# tick-mk-4_6_1.net
KiCad netlist of a schematic drawn in EAGLE
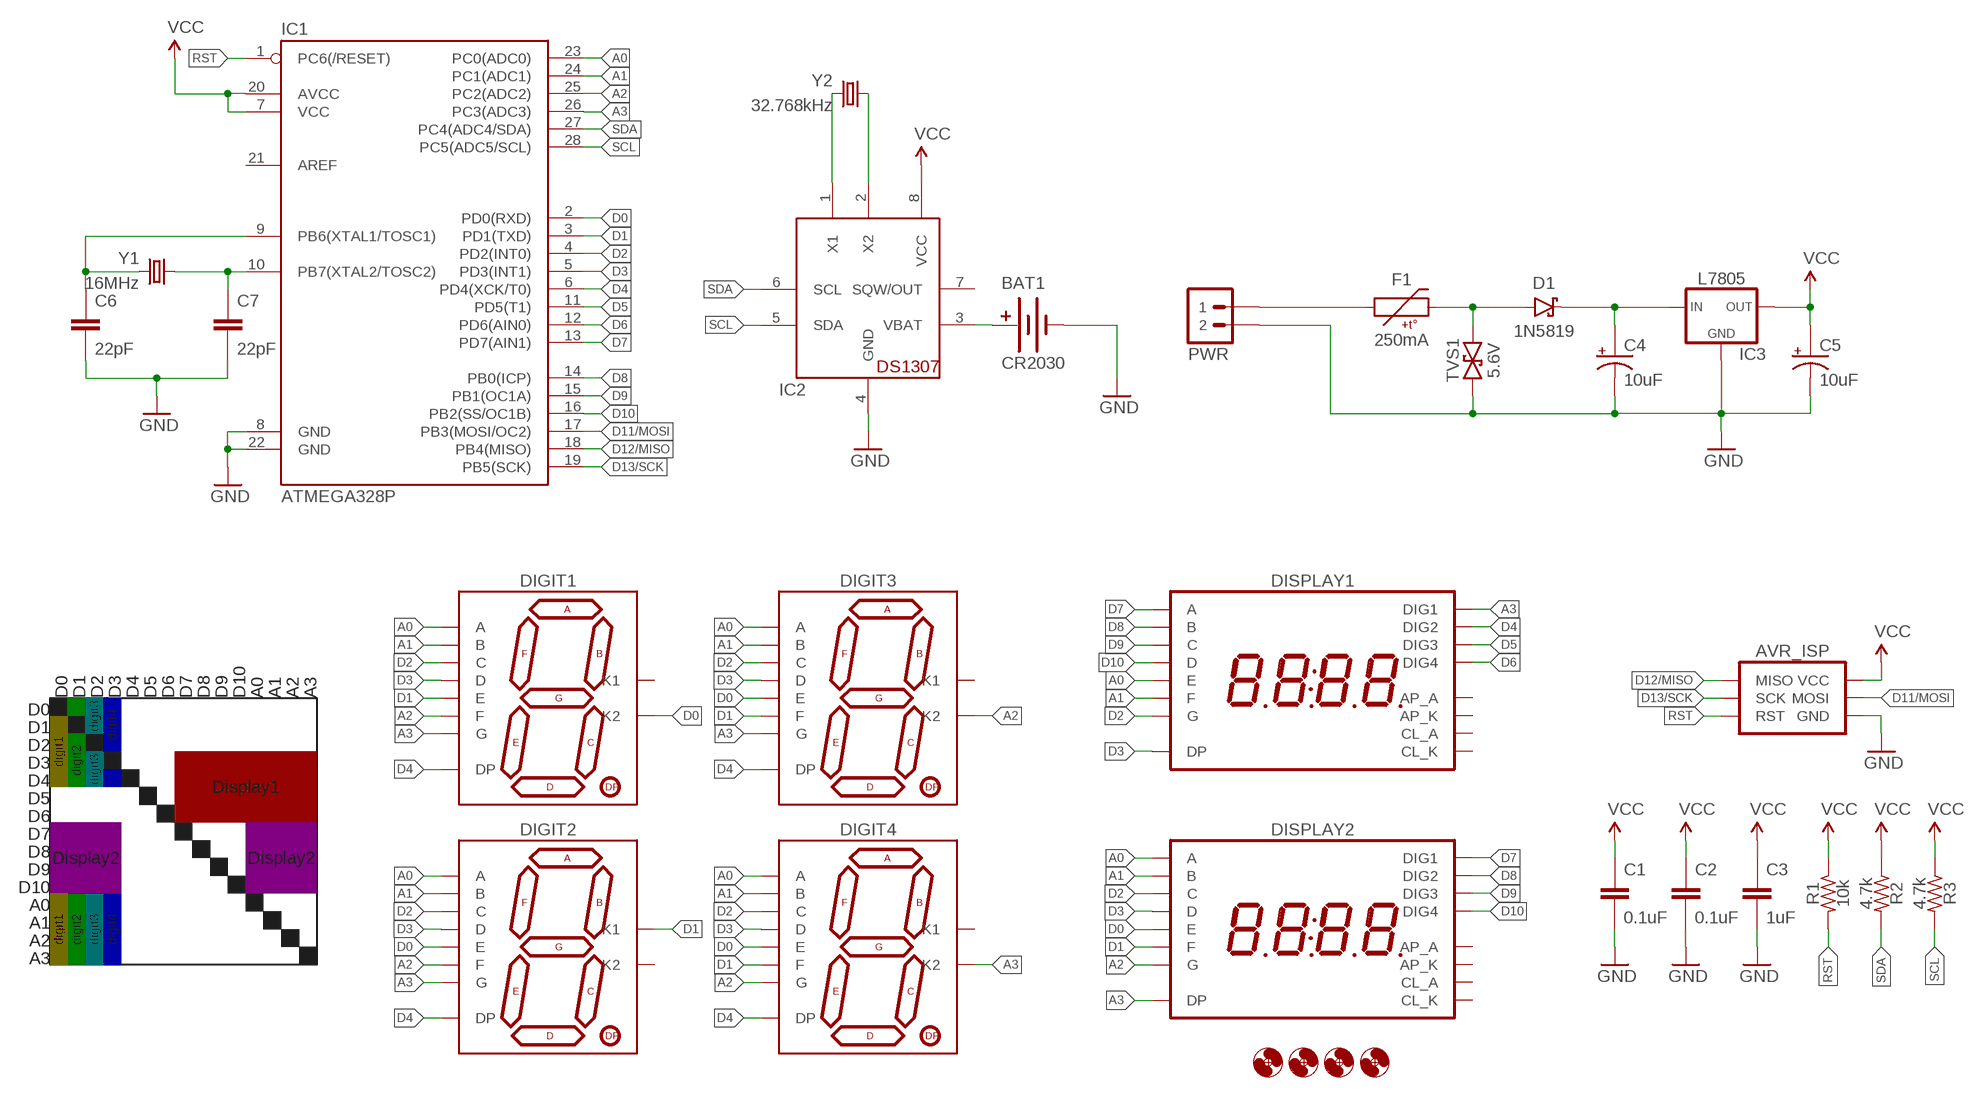
[diagram p0: schematic, sheet 1]

(export (version "E")
  (design (tool "Eeschema 10.0.6"))
  (components
    (comp (ref "AVR_ISP")
      (value "AVR_SPI_PRG_6PTH")
      (footprint "eagle-import:2X3")
      (libsource (lib "eagle-import") (part "AVR_SPI_PRG_6PTH"))
    )
    (comp (ref "BAT1")
      (value "CR2030")
      (footprint "eagle-import:BATTCON_20MM_MINE")
      (libsource (lib "eagle-import") (part "BATTERY20MMSMD-MINE"))
    )
    (comp (ref "C1")
      (value "0.1uF")
      (footprint "eagle-import:C025-024X044")
      (libsource (lib "eagle-import") (part "CAPACITOR-CERAMIC025-024X044"))
    )
    (comp (ref "C2")
      (value "0.1uF")
      (footprint "eagle-import:C025-024X044")
      (libsource (lib "eagle-import") (part "CAPACITOR-CERAMIC025-024X044"))
    )
    (comp (ref "C3")
      (value "1uF")
      (footprint "eagle-import:C025-024X044")
      (libsource (lib "eagle-import") (part "CAPACITOR-CERAMIC025-024X044"))
    )
    (comp (ref "C4")
      (value "10uF")
      (footprint "eagle-import:E2-5")
      (libsource (lib "eagle-import") (part "CAPACITOR-POLARIZEDE2-5"))
    )
    (comp (ref "C5")
      (value "10uF")
      (footprint "eagle-import:E2-5")
      (libsource (lib "eagle-import") (part "CAPACITOR-POLARIZEDE2-5"))
    )
    (comp (ref "C6")
      (value "22pF")
      (footprint "eagle-import:C025-024X044")
      (libsource (lib "eagle-import") (part "CAPACITOR-CERAMIC025-024X044"))
    )
    (comp (ref "C7")
      (value "22pF")
      (footprint "eagle-import:C025-024X044")
      (libsource (lib "eagle-import") (part "CAPACITOR-CERAMIC025-024X044"))
    )
    (comp (ref "D1")
      (value "1N5819")
      (footprint "eagle-import:DIODE-10.16MM")
      (libsource (lib "eagle-import") (part "DIODE-SCHOTTKYPTH-10.16MM"))
    )
    (comp (ref "DIGIT1")
      (value "7SEG_1DIGPTH-25.4MM-BARE")
      (footprint "eagle-import:7SEG_1DIG_25.4MM_NOSILK")
      (libsource (lib "eagle-import") (part "7SEG_1DIGPTH-25.4MM-BARE"))
    )
    (comp (ref "DIGIT2")
      (value "7SEG_1DIGPTH-25.4MM-BARE")
      (footprint "eagle-import:7SEG_1DIG_25.4MM_NOSILK")
      (libsource (lib "eagle-import") (part "7SEG_1DIGPTH-25.4MM-BARE"))
    )
    (comp (ref "DIGIT3")
      (value "7SEG_1DIGPTH-25.4MM-BARE")
      (footprint "eagle-import:7SEG_1DIG_25.4MM_NOSILK")
      (libsource (lib "eagle-import") (part "7SEG_1DIGPTH-25.4MM-BARE"))
    )
    (comp (ref "DIGIT4")
      (value "7SEG_1DIGPTH-25.4MM-BARE")
      (footprint "eagle-import:7SEG_1DIG_25.4MM_NOSILK")
      (libsource (lib "eagle-import") (part "7SEG_1DIGPTH-25.4MM-BARE"))
    )
    (comp (ref "DISPLAY1")
      (value "7SEG_4DIGIT_COLON_APOS")
      (footprint "eagle-import:7SEG_4DIG_10MM")
      (libsource (lib "eagle-import") (part "7SEG_4DIGIT_COLON_APOS"))
    )
    (comp (ref "DISPLAY2")
      (value "7SEG_4DIGIT_COLON_APOS")
      (footprint "eagle-import:7SEG_4DIG_10MM")
      (libsource (lib "eagle-import") (part "7SEG_4DIGIT_COLON_APOS"))
    )
    (comp (ref "F1")
      (value "250mA")
      (footprint "eagle-import:PTC-PTH-5.08MM")
      (libsource (lib "eagle-import") (part "PTCPTH-5.08MM"))
    )
    (comp (ref "H1")
      (value "HOLE#2")
      (footprint "eagle-import:HOLE-#2")
      (libsource (lib "eagle-import") (part "HOLE#2"))
    )
    (comp (ref "H2")
      (value "HOLE#2")
      (footprint "eagle-import:HOLE-#2")
      (libsource (lib "eagle-import") (part "HOLE#2"))
    )
    (comp (ref "H3")
      (value "HOLE#2")
      (footprint "eagle-import:HOLE-#2")
      (libsource (lib "eagle-import") (part "HOLE#2"))
    )
    (comp (ref "H4")
      (value "HOLE#2")
      (footprint "eagle-import:HOLE-#2")
      (libsource (lib "eagle-import") (part "HOLE#2"))
    )
    (comp (ref "IC1")
      (value "ATMEGA328P")
      (footprint "eagle-import:DIL28-3")
      (libsource (lib "eagle-import") (part "ATMEGA328P_PDIP"))
    )
    (comp (ref "IC2")
      (value "DS1307")
      (footprint "eagle-import:DIL08")
      (libsource (lib "eagle-import") (part "DS1307"))
    )
    (comp (ref "IC3")
      (value "L7805")
      (footprint "eagle-import:TO220-IGO-THERMPAD")
      (libsource (lib "eagle-import") (part "V_REG_78XXTO-220-THERMPAD"))
    )
    (comp (ref "PWR")
      (value "M02JST-PTH-VERT")
      (footprint "eagle-import:JST-2-PH-VERT-PTH")
      (libsource (lib "eagle-import") (part "M02JST-PTH-VERT"))
    )
    (comp (ref "R1")
      (value "10k")
      (footprint "eagle-import:RESISTOR-AXIAL-PTH-7.62MM")
      (libsource (lib "eagle-import") (part "RESISTORPTH-AXIAL-7.62MM"))
    )
    (comp (ref "R2")
      (value "4.7k")
      (footprint "eagle-import:RESISTOR-AXIAL-PTH-6.35MM")
      (libsource (lib "eagle-import") (part "RESISTORPTH-AXIAL-6.35MM"))
    )
    (comp (ref "R3")
      (value "4.7k")
      (footprint "eagle-import:RESISTOR-AXIAL-PTH-6.35MM")
      (libsource (lib "eagle-import") (part "RESISTORPTH-AXIAL-6.35MM"))
    )
    (comp (ref "TVS1")
      (value "5.6V")
      (footprint "eagle-import:DO-41-TVS-BI-10.16MM")
      (libsource (lib "eagle-import") (part "TVSDO-41-10.16MM"))
    )
    (comp (ref "Y1")
      (value "16MHz")
      (footprint "eagle-import:HC49U-V")
      (libsource (lib "eagle-import") (part "CRYSTALHC49UV"))
    )
    (comp (ref "Y2")
      (value "32.768kHz")
      (footprint "eagle-import:TC26H")
      (libsource (lib "eagle-import") (part "CRYSTALTC26H"))
    )
  )
  (nets
    (net (code "1") (name "A0") (class "Default")
      (node (ref "DIGIT1") (pin "7") (pinfunction "A_7") (pintype "bidirectional"))
      (node (ref "DIGIT2") (pin "7") (pinfunction "A_7") (pintype "bidirectional"))
      (node (ref "DIGIT3") (pin "7") (pinfunction "A_7") (pintype "bidirectional"))
      (node (ref "DIGIT4") (pin "7") (pinfunction "A_7") (pintype "bidirectional"))
      (node (ref "DISPLAY1") (pin "5") (pinfunction "E_5") (pintype "passive"))
      (node (ref "DISPLAY2") (pin "14") (pinfunction "A_14") (pintype "passive"))
      (node (ref "IC1") (pin "23") (pinfunction "PC0(ADC0)_23") (pintype "bidirectional"))
    )
    (net (code "2") (name "A1") (class "Default")
      (node (ref "DIGIT1") (pin "6") (pinfunction "B_6") (pintype "bidirectional"))
      (node (ref "DIGIT2") (pin "6") (pinfunction "B_6") (pintype "bidirectional"))
      (node (ref "DIGIT3") (pin "6") (pinfunction "B_6") (pintype "bidirectional"))
      (node (ref "DIGIT4") (pin "6") (pinfunction "B_6") (pintype "bidirectional"))
      (node (ref "DISPLAY1") (pin "11") (pinfunction "F_11") (pintype "passive"))
      (node (ref "DISPLAY2") (pin "16") (pinfunction "B_16") (pintype "passive"))
      (node (ref "IC1") (pin "24") (pinfunction "PC1(ADC1)_24") (pintype "bidirectional"))
    )
    (net (code "3") (name "A2") (class "Default")
      (node (ref "DIGIT1") (pin "9") (pinfunction "F_9") (pintype "bidirectional"))
      (node (ref "DIGIT2") (pin "9") (pinfunction "F_9") (pintype "bidirectional"))
      (node (ref "DIGIT3") (pin "8") (pinfunction "K2_8") (pintype "bidirectional"))
      (node (ref "DIGIT4") (pin "10") (pinfunction "G_10") (pintype "bidirectional"))
      (node (ref "DISPLAY2") (pin "15") (pinfunction "G_15") (pintype "passive"))
      (node (ref "IC1") (pin "25") (pinfunction "PC2(ADC2)_25") (pintype "bidirectional"))
    )
    (net (code "4") (name "A3") (class "Default")
      (node (ref "DIGIT1") (pin "10") (pinfunction "G_10") (pintype "bidirectional"))
      (node (ref "DIGIT2") (pin "10") (pinfunction "G_10") (pintype "bidirectional"))
      (node (ref "DIGIT3") (pin "10") (pinfunction "G_10") (pintype "bidirectional"))
      (node (ref "DIGIT4") (pin "8") (pinfunction "K2_8") (pintype "bidirectional"))
      (node (ref "DISPLAY1") (pin "1") (pinfunction "DIG1_1") (pintype "passive"))
      (node (ref "DISPLAY2") (pin "7") (pinfunction "DP_7") (pintype "passive"))
      (node (ref "IC1") (pin "26") (pinfunction "PC3(ADC3)_26") (pintype "bidirectional"))
    )
    (net (code "5") (name "D0") (class "Default")
      (node (ref "DIGIT1") (pin "8") (pinfunction "K2_8") (pintype "bidirectional"))
      (node (ref "DIGIT2") (pin "1") (pinfunction "E_1") (pintype "bidirectional"))
      (node (ref "DIGIT3") (pin "1") (pinfunction "E_1") (pintype "bidirectional"))
      (node (ref "DIGIT4") (pin "1") (pinfunction "E_1") (pintype "bidirectional"))
      (node (ref "DISPLAY2") (pin "5") (pinfunction "E_5") (pintype "passive"))
      (node (ref "IC1") (pin "2") (pinfunction "PD0(RXD)_2") (pintype "bidirectional"))
    )
    (net (code "6") (name "D1") (class "Default")
      (node (ref "DIGIT1") (pin "1") (pinfunction "E_1") (pintype "bidirectional"))
      (node (ref "DIGIT2") (pin "3") (pinfunction "K1_3") (pintype "bidirectional"))
      (node (ref "DIGIT3") (pin "9") (pinfunction "F_9") (pintype "bidirectional"))
      (node (ref "DIGIT4") (pin "9") (pinfunction "F_9") (pintype "bidirectional"))
      (node (ref "DISPLAY2") (pin "11") (pinfunction "F_11") (pintype "passive"))
      (node (ref "IC1") (pin "3") (pinfunction "PD1(TXD)_3") (pintype "bidirectional"))
    )
    (net (code "7") (name "D2") (class "Default")
      (node (ref "DIGIT1") (pin "4") (pinfunction "C_4") (pintype "bidirectional"))
      (node (ref "DIGIT2") (pin "4") (pinfunction "C_4") (pintype "bidirectional"))
      (node (ref "DIGIT3") (pin "4") (pinfunction "C_4") (pintype "bidirectional"))
      (node (ref "DIGIT4") (pin "4") (pinfunction "C_4") (pintype "bidirectional"))
      (node (ref "DISPLAY1") (pin "15") (pinfunction "G_15") (pintype "passive"))
      (node (ref "DISPLAY2") (pin "13") (pinfunction "C_13") (pintype "passive"))
      (node (ref "IC1") (pin "4") (pinfunction "PD2(INT0)_4") (pintype "bidirectional"))
    )
    (net (code "8") (name "D3") (class "Default")
      (node (ref "DIGIT1") (pin "2") (pinfunction "D_2") (pintype "bidirectional"))
      (node (ref "DIGIT2") (pin "2") (pinfunction "D_2") (pintype "bidirectional"))
      (node (ref "DIGIT3") (pin "2") (pinfunction "D_2") (pintype "bidirectional"))
      (node (ref "DIGIT4") (pin "2") (pinfunction "D_2") (pintype "bidirectional"))
      (node (ref "DISPLAY1") (pin "7") (pinfunction "DP_7") (pintype "passive"))
      (node (ref "DISPLAY2") (pin "3") (pinfunction "D_3") (pintype "passive"))
      (node (ref "IC1") (pin "5") (pinfunction "PD3(INT1)_5") (pintype "bidirectional"))
    )
    (net (code "9") (name "D4") (class "Default")
      (node (ref "DIGIT1") (pin "5") (pinfunction "DP_5") (pintype "bidirectional"))
      (node (ref "DIGIT2") (pin "5") (pinfunction "DP_5") (pintype "bidirectional"))
      (node (ref "DIGIT3") (pin "5") (pinfunction "DP_5") (pintype "bidirectional"))
      (node (ref "DIGIT4") (pin "5") (pinfunction "DP_5") (pintype "bidirectional"))
      (node (ref "DISPLAY1") (pin "2") (pinfunction "DIG2_2") (pintype "passive"))
      (node (ref "IC1") (pin "6") (pinfunction "PD4(XCK/T0)_6") (pintype "bidirectional"))
    )
    (net (code "10") (name "D5") (class "Default")
      (node (ref "DISPLAY1") (pin "6") (pinfunction "DIG3_6") (pintype "passive"))
      (node (ref "IC1") (pin "11") (pinfunction "PD5(T1)_11") (pintype "bidirectional"))
    )
    (net (code "11") (name "D6") (class "Default")
      (node (ref "DISPLAY1") (pin "8") (pinfunction "DIG4_8") (pintype "passive"))
      (node (ref "IC1") (pin "12") (pinfunction "PD6(AIN0)_12") (pintype "bidirectional"))
    )
    (net (code "12") (name "D7") (class "Default")
      (node (ref "DISPLAY1") (pin "14") (pinfunction "A_14") (pintype "passive"))
      (node (ref "DISPLAY2") (pin "1") (pinfunction "DIG1_1") (pintype "passive"))
      (node (ref "IC1") (pin "13") (pinfunction "PD7(AIN1)_13") (pintype "bidirectional"))
    )
    (net (code "13") (name "D8") (class "Default")
      (node (ref "DISPLAY1") (pin "16") (pinfunction "B_16") (pintype "passive"))
      (node (ref "DISPLAY2") (pin "2") (pinfunction "DIG2_2") (pintype "passive"))
      (node (ref "IC1") (pin "14") (pinfunction "PB0(ICP)_14") (pintype "bidirectional"))
    )
    (net (code "14") (name "D9") (class "Default")
      (node (ref "DISPLAY1") (pin "13") (pinfunction "C_13") (pintype "passive"))
      (node (ref "DISPLAY2") (pin "6") (pinfunction "DIG3_6") (pintype "passive"))
      (node (ref "IC1") (pin "15") (pinfunction "PB1(OC1A)_15") (pintype "bidirectional"))
    )
    (net (code "15") (name "D10") (class "Default")
      (node (ref "DISPLAY1") (pin "3") (pinfunction "D_3") (pintype "passive"))
      (node (ref "DISPLAY2") (pin "8") (pinfunction "DIG4_8") (pintype "passive"))
      (node (ref "IC1") (pin "16") (pinfunction "PB2(SS/OC1B)_16") (pintype "bidirectional"))
    )
    (net (code "16") (name "D11{slash}MOSI") (class "Default")
      (node (ref "AVR_ISP") (pin "4") (pinfunction "MOSI_4") (pintype "passive"))
      (node (ref "IC1") (pin "17") (pinfunction "PB3(MOSI/OC2)_17") (pintype "bidirectional"))
    )
    (net (code "17") (name "D12{slash}MISO") (class "Default")
      (node (ref "AVR_ISP") (pin "1") (pinfunction "MISO_1") (pintype "passive"))
      (node (ref "IC1") (pin "18") (pinfunction "PB4(MISO)_18") (pintype "bidirectional"))
    )
    (net (code "18") (name "D13{slash}SCK") (class "Default")
      (node (ref "AVR_ISP") (pin "3") (pinfunction "SCK_3") (pintype "passive"))
      (node (ref "IC1") (pin "19") (pinfunction "PB5(SCK)_19") (pintype "bidirectional"))
    )
    (net (code "19") (name "GND") (class "Default")
      (node (ref "AVR_ISP") (pin "6") (pinfunction "GND_6") (pintype "passive"))
      (node (ref "BAT1") (pin "BOTTOM") (pinfunction "-_BOTTOM") (pintype "power_in"))
      (node (ref "C1") (pin "2") (pinfunction "2_2") (pintype "passive"))
      (node (ref "C2") (pin "2") (pinfunction "2_2") (pintype "passive"))
      (node (ref "C3") (pin "2") (pinfunction "2_2") (pintype "passive"))
      (node (ref "C4") (pin "-") (pinfunction "-_-") (pintype "passive"))
      (node (ref "C5") (pin "-") (pinfunction "-_-") (pintype "passive"))
      (node (ref "C6") (pin "2") (pinfunction "2_2") (pintype "passive"))
      (node (ref "C7") (pin "2") (pinfunction "2_2") (pintype "passive"))
      (node (ref "IC1") (pin "22") (pinfunction "GND_22") (pintype "bidirectional"))
      (node (ref "IC1") (pin "8") (pinfunction "GND_8") (pintype "bidirectional"))
      (node (ref "IC2") (pin "4") (pinfunction "GND_4") (pintype "power_in"))
      (node (ref "IC3") (pin "4") (pinfunction "GND_4") (pintype "bidirectional"))
      (node (ref "IC3") (pin "GND") (pinfunction "GND_GND") (pintype "bidirectional"))
      (node (ref "PWR") (pin "2") (pinfunction "2_2") (pintype "passive"))
      (node (ref "TVS1") (pin "P$1") (pinfunction "1_P$1") (pintype "passive"))
    )
    (net (code "20") (name "Net-(C4-Pad+)") (class "Default")
      (node (ref "C4") (pin "+") (pinfunction "+_+") (pintype "passive"))
      (node (ref "D1") (pin "C") (pinfunction "C_C") (pintype "passive"))
      (node (ref "IC3") (pin "IN") (pinfunction "IN_IN") (pintype "bidirectional"))
    )
    (net (code "21") (name "Net-(F1-1)") (class "Default")
      (node (ref "F1") (pin "P$1") (pinfunction "1_P$1") (pintype "passive"))
      (node (ref "PWR") (pin "1") (pinfunction "1_1") (pintype "passive"))
    )
    (net (code "22") (name "Net-(F1-2)") (class "Default")
      (node (ref "D1") (pin "A") (pinfunction "A_A") (pintype "passive"))
      (node (ref "F1") (pin "P$2") (pinfunction "2_P$2") (pintype "passive"))
      (node (ref "TVS1") (pin "P$2") (pinfunction "2_P$2") (pintype "passive"))
    )
    (net (code "23") (name "Net-(IC1-PB6(XTAL1{slash}TOSC1))") (class "Default")
      (node (ref "C6") (pin "1") (pinfunction "1_1") (pintype "passive"))
      (node (ref "IC1") (pin "9") (pinfunction "PB6(XTAL1/TOSC1)_9") (pintype "bidirectional"))
      (node (ref "Y1") (pin "2") (pinfunction "2_2") (pintype "passive"))
    )
    (net (code "24") (name "Net-(IC1-PB7(XTAL2{slash}TOSC2))") (class "Default")
      (node (ref "C7") (pin "1") (pinfunction "1_1") (pintype "passive"))
      (node (ref "IC1") (pin "10") (pinfunction "PB7(XTAL2/TOSC2)_10") (pintype "bidirectional"))
      (node (ref "Y1") (pin "1") (pinfunction "1_1") (pintype "passive"))
    )
    (net (code "25") (name "Net-(IC2-VBAT)") (class "Default")
      (node (ref "BAT1") (pin "TOP@1") (pinfunction "+_TOP@1") (pintype "power_in"))
      (node (ref "BAT1") (pin "TOP@2") (pinfunction "+_TOP@2") (pintype "power_in"))
      (node (ref "IC2") (pin "3") (pinfunction "VBAT_3") (pintype "power_in"))
    )
    (net (code "26") (name "Net-(IC2-X1)") (class "Default")
      (node (ref "IC2") (pin "1") (pinfunction "X1_1") (pintype "passive"))
      (node (ref "Y2") (pin "2") (pinfunction "2_2") (pintype "passive"))
    )
    (net (code "27") (name "Net-(IC2-X2)") (class "Default")
      (node (ref "IC2") (pin "2") (pinfunction "X2_2") (pintype "passive"))
      (node (ref "Y2") (pin "1") (pinfunction "1_1") (pintype "passive"))
    )
    (net (code "28") (name "RST") (class "Default")
      (node (ref "AVR_ISP") (pin "5") (pinfunction "RST_5") (pintype "passive"))
      (node (ref "IC1") (pin "1") (pinfunction "PC6(/RESET)_1") (pintype "bidirectional"))
      (node (ref "R1") (pin "P$2") (pinfunction "2_P$2") (pintype "passive"))
    )
    (net (code "29") (name "SCL") (class "Default")
      (node (ref "IC1") (pin "28") (pinfunction "PC5(ADC5/SCL)_28") (pintype "bidirectional"))
      (node (ref "IC2") (pin "5") (pinfunction "SDA_5") (pintype "bidirectional"))
      (node (ref "R3") (pin "P$2") (pinfunction "2_P$2") (pintype "passive"))
    )
    (net (code "30") (name "SDA") (class "Default")
      (node (ref "IC1") (pin "27") (pinfunction "PC4(ADC4/SDA)_27") (pintype "bidirectional"))
      (node (ref "IC2") (pin "6") (pinfunction "SCL_6") (pintype "bidirectional"))
      (node (ref "R2") (pin "P$2") (pinfunction "2_P$2") (pintype "passive"))
    )
    (net (code "31") (name "VCC") (class "Default")
      (node (ref "AVR_ISP") (pin "2") (pinfunction "VCC_2") (pintype "passive"))
      (node (ref "C1") (pin "1") (pinfunction "1_1") (pintype "passive"))
      (node (ref "C2") (pin "1") (pinfunction "1_1") (pintype "passive"))
      (node (ref "C3") (pin "1") (pinfunction "1_1") (pintype "passive"))
      (node (ref "C5") (pin "+") (pinfunction "+_+") (pintype "passive"))
      (node (ref "IC1") (pin "20") (pinfunction "AVCC_20") (pintype "bidirectional"))
      (node (ref "IC1") (pin "7") (pinfunction "VCC_7") (pintype "bidirectional"))
      (node (ref "IC2") (pin "8") (pinfunction "VCC_8") (pintype "power_in"))
      (node (ref "IC3") (pin "OUT") (pinfunction "OUT_OUT") (pintype "bidirectional"))
      (node (ref "R1") (pin "P$1") (pinfunction "1_P$1") (pintype "passive"))
      (node (ref "R2") (pin "P$1") (pinfunction "1_P$1") (pintype "passive"))
      (node (ref "R3") (pin "P$1") (pinfunction "1_P$1") (pintype "passive"))
    )
    (net (code "32") (name "unconnected-(DIGIT1-K1-Pad3)") (class "Default")
      (node (ref "DIGIT1") (pin "3") (pinfunction "K1_3") (pintype "bidirectional"))
    )
    (net (code "33") (name "unconnected-(DIGIT2-K2-Pad8)") (class "Default")
      (node (ref "DIGIT2") (pin "8") (pinfunction "K2_8") (pintype "bidirectional"))
    )
    (net (code "34") (name "unconnected-(DIGIT3-K1-Pad3)") (class "Default")
      (node (ref "DIGIT3") (pin "3") (pinfunction "K1_3") (pintype "bidirectional"))
    )
    (net (code "35") (name "unconnected-(DIGIT4-K1-Pad3)") (class "Default")
      (node (ref "DIGIT4") (pin "3") (pinfunction "K1_3") (pintype "bidirectional"))
    )
    (net (code "36") (name "unconnected-(DISPLAY1-AP_A-Pad10)") (class "Default")
      (node (ref "DISPLAY1") (pin "10") (pinfunction "AP_A_10") (pintype "bidirectional"))
    )
    (net (code "37") (name "unconnected-(DISPLAY1-AP_K-Pad9)") (class "Default")
      (node (ref "DISPLAY1") (pin "9") (pinfunction "AP_K_9") (pintype "bidirectional"))
    )
    (net (code "38") (name "unconnected-(DISPLAY1-CL_A-Pad4)") (class "Default")
      (node (ref "DISPLAY1") (pin "4") (pinfunction "CL_A_4") (pintype "passive"))
    )
    (net (code "39") (name "unconnected-(DISPLAY1-CL_K-Pad12)") (class "Default")
      (node (ref "DISPLAY1") (pin "12") (pinfunction "CL_K_12") (pintype "passive"))
    )
    (net (code "40") (name "unconnected-(DISPLAY2-AP_A-Pad10)") (class "Default")
      (node (ref "DISPLAY2") (pin "10") (pinfunction "AP_A_10") (pintype "bidirectional"))
    )
    (net (code "41") (name "unconnected-(DISPLAY2-AP_K-Pad9)") (class "Default")
      (node (ref "DISPLAY2") (pin "9") (pinfunction "AP_K_9") (pintype "bidirectional"))
    )
    (net (code "42") (name "unconnected-(DISPLAY2-CL_A-Pad4)") (class "Default")
      (node (ref "DISPLAY2") (pin "4") (pinfunction "CL_A_4") (pintype "passive"))
    )
    (net (code "43") (name "unconnected-(DISPLAY2-CL_K-Pad12)") (class "Default")
      (node (ref "DISPLAY2") (pin "12") (pinfunction "CL_K_12") (pintype "passive"))
    )
    (net (code "44") (name "unconnected-(IC1-AREF-Pad21)") (class "Default")
      (node (ref "IC1") (pin "21") (pinfunction "AREF_21") (pintype "bidirectional"))
    )
    (net (code "45") (name "unconnected-(IC2-SQW{slash}OUT-Pad7)") (class "Default")
      (node (ref "IC2") (pin "7") (pinfunction "SQW/OUT_7") (pintype "bidirectional"))
    )
  )
)
